# MoteinoM0_mic_v0_3.net
KiCad netlist of a schematic drawn in EAGLE
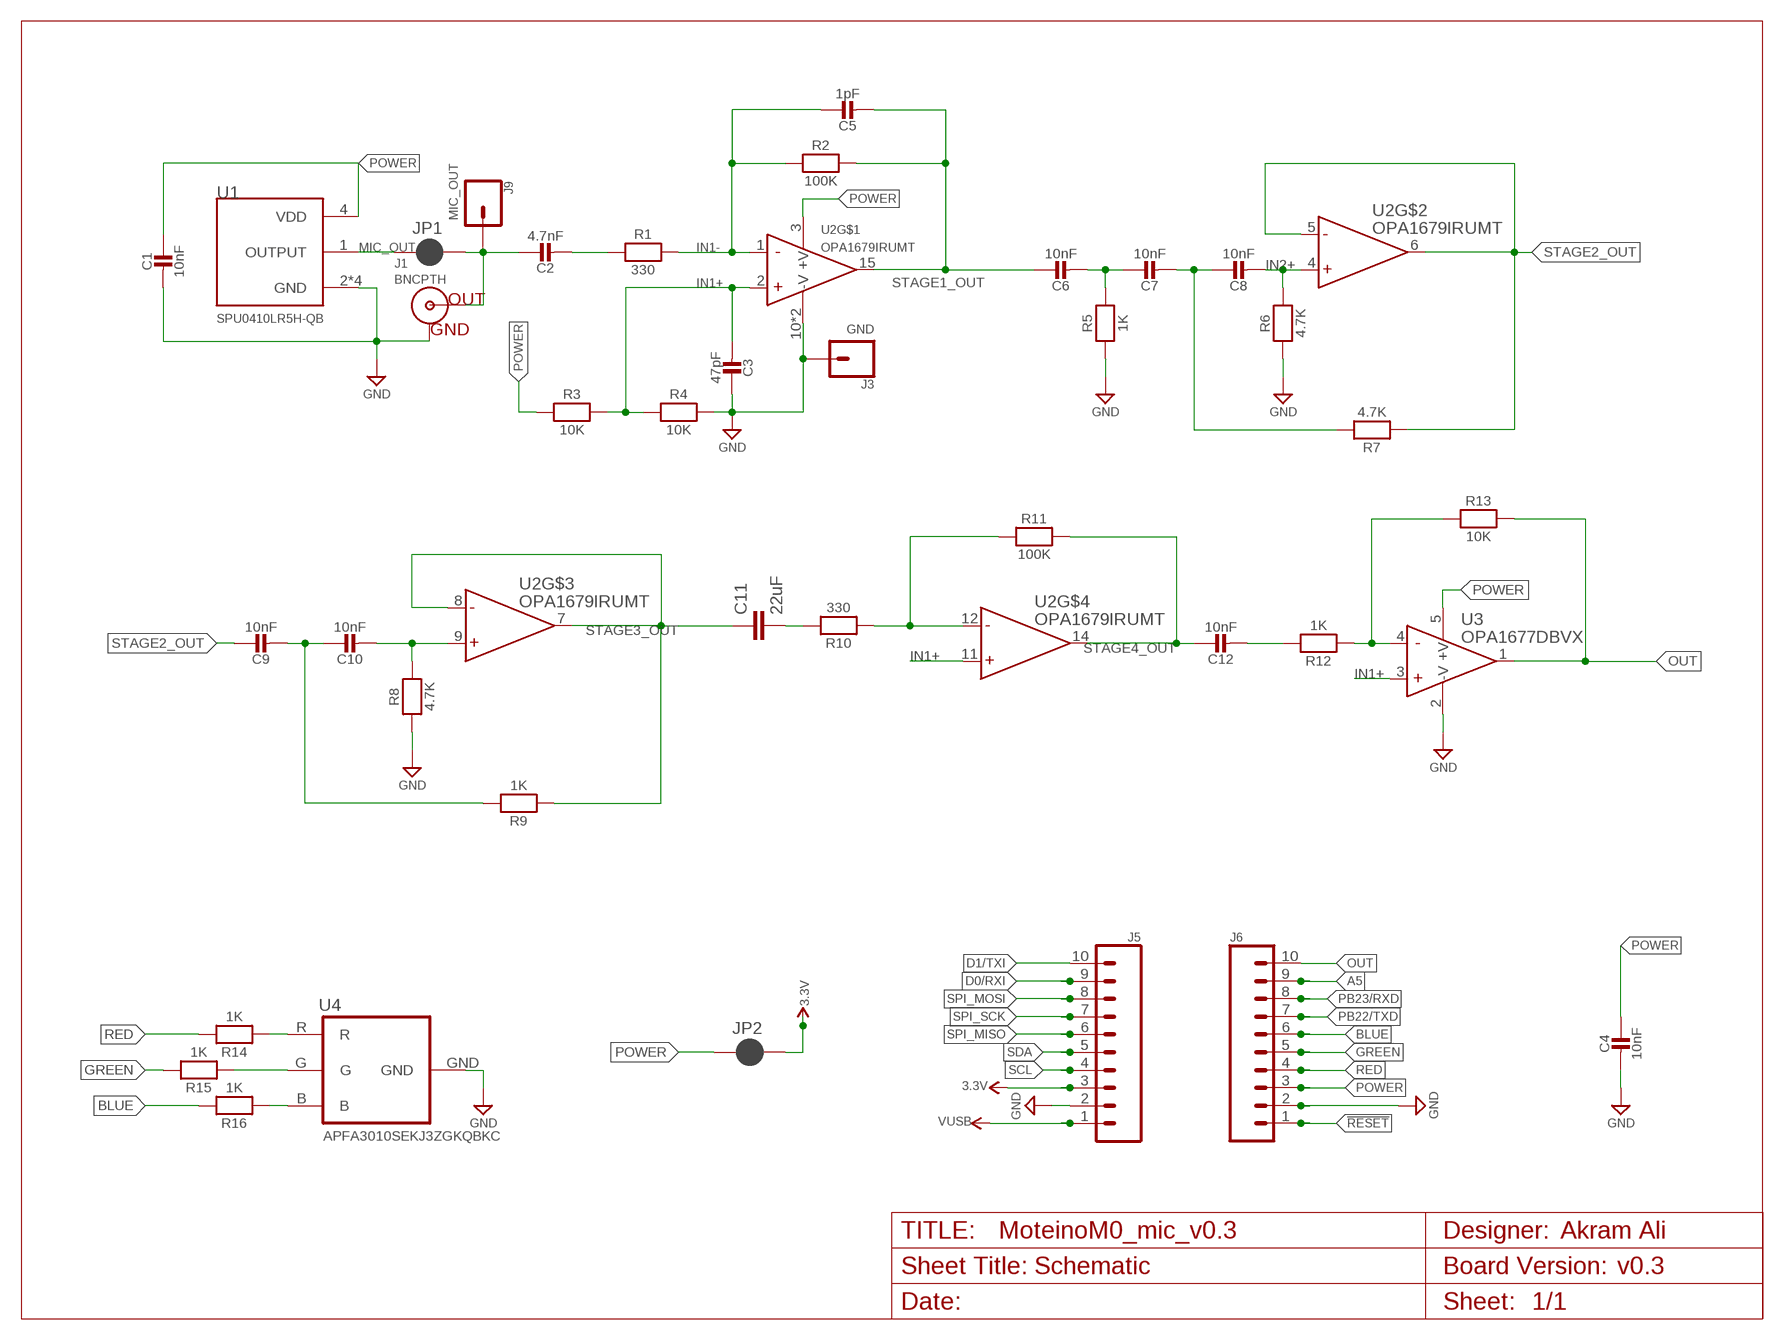
[diagram p0: schematic, sheet 1]

(export (version "E")
  (design (tool "Eeschema 10.0.6"))
  (components
    (comp (ref "C1")
      (value "10nF")
      (footprint "eagle-import:MICROBUILDER__0402MP")
      (fields (field (name "MPN") "GRM155R71H104KE14J"))
      (libsource (lib "eagle-import") (part "MICROBUILDER_CAP_CERAMIC_0402MP"))
    )
    (comp (ref "C2")
      (value "4.7nF")
      (footprint "eagle-import:MICROBUILDER__0402MP")
      (fields (field (name "MPN") "GRM155R71H104KE14J"))
      (libsource (lib "eagle-import") (part "MICROBUILDER_CAP_CERAMIC_0402MP"))
    )
    (comp (ref "C3")
      (value "47pF")
      (footprint "eagle-import:MICROBUILDER__0402MP")
      (fields (field (name "MPN") "GRM155R71H104KE14J"))
      (libsource (lib "eagle-import") (part "MICROBUILDER_CAP_CERAMIC_0402MP"))
    )
    (comp (ref "C4")
      (value "10nF")
      (footprint "eagle-import:MICROBUILDER__0402MP")
      (fields (field (name "MPN") "GRM155R71H104KE14J"))
      (libsource (lib "eagle-import") (part "MICROBUILDER_CAP_CERAMIC_0402MP"))
    )
    (comp (ref "C5")
      (value "1pF")
      (footprint "eagle-import:MICROBUILDER__0402MP")
      (fields (field (name "MPN") "GRM155R71H104KE14J"))
      (libsource (lib "eagle-import") (part "MICROBUILDER_CAP_CERAMIC_0402MP"))
    )
    (comp (ref "C6")
      (value "10nF")
      (footprint "eagle-import:MICROBUILDER__0402MP")
      (fields (field (name "MPN") "GRM155R71H104KE14J"))
      (libsource (lib "eagle-import") (part "MICROBUILDER_CAP_CERAMIC_0402MP"))
    )
    (comp (ref "C7")
      (value "10nF")
      (footprint "eagle-import:MICROBUILDER__0402MP")
      (fields (field (name "MPN") "GRM155R71H104KE14J"))
      (libsource (lib "eagle-import") (part "MICROBUILDER_CAP_CERAMIC_0402MP"))
    )
    (comp (ref "C8")
      (value "10nF")
      (footprint "eagle-import:MICROBUILDER__0402MP")
      (fields (field (name "MPN") "GRM155R71H104KE14J"))
      (libsource (lib "eagle-import") (part "MICROBUILDER_CAP_CERAMIC_0402MP"))
    )
    (comp (ref "C9")
      (value "10nF")
      (footprint "eagle-import:MICROBUILDER__0402MP")
      (fields (field (name "MPN") "GRM155R71H104KE14J"))
      (libsource (lib "eagle-import") (part "MICROBUILDER_CAP_CERAMIC_0402MP"))
    )
    (comp (ref "C10")
      (value "10nF")
      (footprint "eagle-import:MICROBUILDER__0402MP")
      (fields (field (name "MPN") "GRM155R71H104KE14J"))
      (libsource (lib "eagle-import") (part "MICROBUILDER_CAP_CERAMIC_0402MP"))
    )
    (comp (ref "C11")
      (value "22uF")
      (footprint "eagle-import:0805")
      (libsource (lib "eagle-import") (part "CAP0805"))
    )
    (comp (ref "C12")
      (value "10nF")
      (footprint "eagle-import:MICROBUILDER__0402MP")
      (fields (field (name "MPN") "GRM155R71H104KE14J"))
      (libsource (lib "eagle-import") (part "MICROBUILDER_CAP_CERAMIC_0402MP"))
    )
    (comp (ref "J1")
      (value "BNCPTH")
      (footprint "eagle-import:BNC")
      (libsource (lib "eagle-import") (part "BNCPTH"))
    )
    (comp (ref "J3")
      (value "GND")
      (footprint "eagle-import:1X01")
      (libsource (lib "eagle-import") (part "CONN_01"))
    )
    (comp (ref "J5")
      (value "CONN_10NO_SILK_PTH_FEMALE")
      (footprint "eagle-import:1X10_NO_SILK")
      (libsource (lib "eagle-import") (part "CONN_10NO_SILK_PTH_FEMALE"))
    )
    (comp (ref "J6")
      (value "CONN_10NO_SILK_PTH_FEMALE")
      (footprint "eagle-import:1X10_NO_SILK")
      (libsource (lib "eagle-import") (part "CONN_10NO_SILK_PTH_FEMALE"))
    )
    (comp (ref "J9")
      (value "MIC_OUT")
      (footprint "eagle-import:1X01")
      (libsource (lib "eagle-import") (part "CONN_01"))
    )
    (comp (ref "JP1")
      (value "JUMPER-SMT_2_NC_PASTE_SILK")
      (footprint "eagle-import:SMT-JUMPER_2_NC_PASTE_SILK")
      (libsource (lib "eagle-import") (part "JUMPER-SMT_2_NC_PASTE_SILK"))
    )
    (comp (ref "JP2")
      (value "JUMPER-SMT_2_NC_PASTE_SILK")
      (footprint "eagle-import:SMT-JUMPER_2_NC_PASTE_SILK")
      (libsource (lib "eagle-import") (part "JUMPER-SMT_2_NC_PASTE_SILK"))
    )
    (comp (ref "R1")
      (value "330")
      (footprint "eagle-import:MICROBUILDER__0402MP")
      (fields (field (name "MPN") "RC0402FR-074K7P"))
      (libsource (lib "eagle-import") (part "MICROBUILDER_RESISTOR_0402MP"))
    )
    (comp (ref "R2")
      (value "100K")
      (footprint "eagle-import:MICROBUILDER__0402MP")
      (fields (field (name "MPN") "RC0402FR-074K7P"))
      (libsource (lib "eagle-import") (part "MICROBUILDER_RESISTOR_0402MP"))
    )
    (comp (ref "R3")
      (value "10K")
      (footprint "eagle-import:MICROBUILDER__0402MP")
      (fields (field (name "MPN") "RC0402FR-074K7P"))
      (libsource (lib "eagle-import") (part "MICROBUILDER_RESISTOR_0402MP"))
    )
    (comp (ref "R4")
      (value "10K")
      (footprint "eagle-import:MICROBUILDER__0402MP")
      (fields (field (name "MPN") "RC0402FR-074K7P"))
      (libsource (lib "eagle-import") (part "MICROBUILDER_RESISTOR_0402MP"))
    )
    (comp (ref "R5")
      (value "1K")
      (footprint "eagle-import:MICROBUILDER__0402MP")
      (fields (field (name "MPN") "RC0402FR-074K7P"))
      (libsource (lib "eagle-import") (part "MICROBUILDER_RESISTOR_0402MP"))
    )
    (comp (ref "R6")
      (value "4.7K")
      (footprint "eagle-import:MICROBUILDER__0402MP")
      (fields (field (name "MPN") "RC0402FR-074K7P"))
      (libsource (lib "eagle-import") (part "MICROBUILDER_RESISTOR_0402MP"))
    )
    (comp (ref "R7")
      (value "4.7K")
      (footprint "eagle-import:MICROBUILDER__0402MP")
      (fields (field (name "MPN") "RC0402FR-074K7P"))
      (libsource (lib "eagle-import") (part "MICROBUILDER_RESISTOR_0402MP"))
    )
    (comp (ref "R8")
      (value "4.7K")
      (footprint "eagle-import:MICROBUILDER__0402MP")
      (fields (field (name "MPN") "RC0402FR-074K7P"))
      (libsource (lib "eagle-import") (part "MICROBUILDER_RESISTOR_0402MP"))
    )
    (comp (ref "R9")
      (value "1K")
      (footprint "eagle-import:MICROBUILDER__0402MP")
      (fields (field (name "MPN") "RC0402FR-074K7P"))
      (libsource (lib "eagle-import") (part "MICROBUILDER_RESISTOR_0402MP"))
    )
    (comp (ref "R10")
      (value "330")
      (footprint "eagle-import:MICROBUILDER__0402MP")
      (fields (field (name "MPN") "RC0402FR-074K7P"))
      (libsource (lib "eagle-import") (part "MICROBUILDER_RESISTOR_0402MP"))
    )
    (comp (ref "R11")
      (value "100K")
      (footprint "eagle-import:MICROBUILDER__0402MP")
      (fields (field (name "MPN") "RC0402FR-074K7P"))
      (libsource (lib "eagle-import") (part "MICROBUILDER_RESISTOR_0402MP"))
    )
    (comp (ref "R12")
      (value "1K")
      (footprint "eagle-import:MICROBUILDER__0402MP")
      (fields (field (name "MPN") "RC0402FR-074K7P"))
      (libsource (lib "eagle-import") (part "MICROBUILDER_RESISTOR_0402MP"))
    )
    (comp (ref "R13")
      (value "10K")
      (footprint "eagle-import:MICROBUILDER__0402MP")
      (fields (field (name "MPN") "RC0402FR-074K7P"))
      (libsource (lib "eagle-import") (part "MICROBUILDER_RESISTOR_0402MP"))
    )
    (comp (ref "R14")
      (value "1K")
      (footprint "eagle-import:MICROBUILDER__0402MP")
      (fields (field (name "MPN") "RC0402FR-074K7P"))
      (libsource (lib "eagle-import") (part "MICROBUILDER_RESISTOR_0402MP"))
    )
    (comp (ref "R15")
      (value "1K")
      (footprint "eagle-import:MICROBUILDER__0402MP")
      (fields (field (name "MPN") "RC0402FR-074K7P"))
      (libsource (lib "eagle-import") (part "MICROBUILDER_RESISTOR_0402MP"))
    )
    (comp (ref "R16")
      (value "1K")
      (footprint "eagle-import:MICROBUILDER__0402MP")
      (fields (field (name "MPN") "RC0402FR-074K7P"))
      (libsource (lib "eagle-import") (part "MICROBUILDER_RESISTOR_0402MP"))
    )
    (comp (ref "U1")
      (value "SPU0410LR5H-QB")
      (footprint "eagle-import:XDCR_SPU0410LR5H-QB")
      (fields (field (name "MF") "Knowles"))
      (libsource (lib "eagle-import") (part "SPU0410LR5H-QB"))
    )
    (comp (ref "U2")
      (value "OPA1679IRUMT")
      (footprint "eagle-import:QFN65P400X400X80-17N")
      (libsource (lib "eagle-import") (part "OPA1679IRUMT"))
    )
    (comp (ref "U3")
      (value "OPA1677DBVX")
      (footprint "eagle-import:SOT23-5")
      (libsource (lib "eagle-import") (part "OPA1677DBVX"))
    )
    (comp (ref "U4")
      (value "APFA3010SEKJ3ZGKQBKC")
      (footprint "eagle-import:SMD-RA-4")
      (libsource (lib "eagle-import") (part "APFA3010SEKJ3ZGKQBKC"))
    )
  )
  (nets
    (net (code "1") (name "/IN1+") (class "Default")
      (node (ref "C3") (pin "2") (pinfunction "2_2") (pintype "passive"))
      (node (ref "R3") (pin "2") (pinfunction "2_2") (pintype "passive"))
      (node (ref "R4") (pin "1") (pinfunction "1_1") (pintype "passive"))
      (node (ref "U2") (pin "11") (pinfunction "+IN_11") (pintype "input"))
      (node (ref "U2") (pin "2") (pinfunction "+IN_2") (pintype "input"))
      (node (ref "U3") (pin "3") (pinfunction "+IN_3") (pintype "input"))
    )
    (net (code "2") (name "/IN1-") (class "Default")
      (node (ref "C5") (pin "1") (pinfunction "1_1") (pintype "passive"))
      (node (ref "R1") (pin "2") (pinfunction "2_2") (pintype "passive"))
      (node (ref "R2") (pin "1") (pinfunction "1_1") (pintype "passive"))
      (node (ref "U2") (pin "1") (pinfunction "-IN_1") (pintype "input"))
    )
    (net (code "3") (name "/IN2+") (class "Default")
      (node (ref "C8") (pin "2") (pinfunction "2_2") (pintype "passive"))
      (node (ref "R6") (pin "2") (pinfunction "2_2") (pintype "passive"))
      (node (ref "U2") (pin "4") (pinfunction "+IN_4") (pintype "input"))
    )
    (net (code "4") (name "/MIC_OUT") (class "Default")
      (node (ref "C2") (pin "1") (pinfunction "1_1") (pintype "passive"))
      (node (ref "J1") (pin "S") (pinfunction "OUT_S") (pintype "bidirectional"))
      (node (ref "J9") (pin "1") (pinfunction "1_1") (pintype "passive"))
      (node (ref "JP1") (pin "2") (pinfunction "2_2") (pintype "passive"))
    )
    (net (code "5") (name "/STAGE1_OUT") (class "Default")
      (node (ref "C5") (pin "2") (pinfunction "2_2") (pintype "passive"))
      (node (ref "C6") (pin "1") (pinfunction "1_1") (pintype "passive"))
      (node (ref "R2") (pin "2") (pinfunction "2_2") (pintype "passive"))
      (node (ref "U2") (pin "15") (pinfunction "OUT_15") (pintype "output"))
    )
    (net (code "6") (name "/STAGE3_OUT") (class "Default")
      (node (ref "C11") (pin "1") (pinfunction "1_1") (pintype "passive"))
      (node (ref "R9") (pin "1") (pinfunction "1_1") (pintype "passive"))
      (node (ref "U2") (pin "7") (pinfunction "OUT_7") (pintype "output"))
      (node (ref "U2") (pin "8") (pinfunction "-IN_8") (pintype "input"))
    )
    (net (code "7") (name "/STAGE4_OUT") (class "Default")
      (node (ref "C12") (pin "1") (pinfunction "1_1") (pintype "passive"))
      (node (ref "R11") (pin "2") (pinfunction "2_2") (pintype "passive"))
      (node (ref "U2") (pin "14") (pinfunction "OUT_14") (pintype "output"))
    )
    (net (code "8") (name "/~{RESET}") (class "Default")
      (node (ref "J6") (pin "1") (pinfunction "1_1") (pintype "passive"))
    )
    (net (code "9") (name "3.3V") (class "Default")
      (node (ref "J5") (pin "3") (pinfunction "3_3") (pintype "passive"))
      (node (ref "JP2") (pin "2") (pinfunction "2_2") (pintype "passive"))
    )
    (net (code "10") (name "A5") (class "Default")
      (node (ref "J6") (pin "9") (pinfunction "9_9") (pintype "passive"))
    )
    (net (code "11") (name "BLUE") (class "Default")
      (node (ref "J6") (pin "6") (pinfunction "6_6") (pintype "passive"))
      (node (ref "R16") (pin "2") (pinfunction "2_2") (pintype "passive"))
    )
    (net (code "12") (name "D0{slash}RXI") (class "Default")
      (node (ref "J5") (pin "9") (pinfunction "9_9") (pintype "passive"))
    )
    (net (code "13") (name "D1{slash}TXI") (class "Default")
      (node (ref "J5") (pin "10") (pinfunction "10_10") (pintype "passive"))
    )
    (net (code "14") (name "GND") (class "Default")
      (node (ref "C1") (pin "2") (pinfunction "2_2") (pintype "passive"))
      (node (ref "C3") (pin "1") (pinfunction "1_1") (pintype "passive"))
      (node (ref "C4") (pin "2") (pinfunction "2_2") (pintype "passive"))
      (node (ref "J1") (pin "GND") (pinfunction "GND_GND") (pintype "bidirectional"))
      (node (ref "J3") (pin "1") (pinfunction "1_1") (pintype "passive"))
      (node (ref "J5") (pin "2") (pinfunction "2_2") (pintype "passive"))
      (node (ref "J6") (pin "2") (pinfunction "2_2") (pintype "passive"))
      (node (ref "R4") (pin "2") (pinfunction "2_2") (pintype "passive"))
      (node (ref "R5") (pin "1") (pinfunction "1_1") (pintype "passive"))
      (node (ref "R6") (pin "1") (pinfunction "1_1") (pintype "passive"))
      (node (ref "R8") (pin "1") (pinfunction "1_1") (pintype "passive"))
      (node (ref "U1") (pin "2") (pinfunction "GND_2") (pintype "power_in"))
      (node (ref "U1") (pin "3") (pinfunction "GND_3") (pintype "power_in"))
      (node (ref "U1") (pin "5") (pinfunction "GND_5") (pintype "power_in"))
      (node (ref "U1") (pin "6") (pinfunction "GND_6") (pintype "power_in"))
      (node (ref "U2") (pin "10") (pinfunction "-V_10") (pintype "power_in"))
      (node (ref "U2") (pin "17") (pinfunction "-V_17") (pintype "power_in"))
      (node (ref "U3") (pin "2") (pinfunction "-V_2") (pintype "power_in"))
      (node (ref "U4") (pin "GND") (pinfunction "GND_GND") (pintype "bidirectional"))
    )
    (net (code "15") (name "GREEN") (class "Default")
      (node (ref "J6") (pin "5") (pinfunction "5_5") (pintype "passive"))
      (node (ref "R15") (pin "2") (pinfunction "2_2") (pintype "passive"))
    )
    (net (code "16") (name "Net-(C2-Pad2)") (class "Default")
      (node (ref "C2") (pin "2") (pinfunction "2_2") (pintype "passive"))
      (node (ref "R1") (pin "1") (pinfunction "1_1") (pintype "passive"))
    )
    (net (code "17") (name "Net-(C6-Pad2)") (class "Default")
      (node (ref "C6") (pin "2") (pinfunction "2_2") (pintype "passive"))
      (node (ref "C7") (pin "1") (pinfunction "1_1") (pintype "passive"))
      (node (ref "R5") (pin "2") (pinfunction "2_2") (pintype "passive"))
    )
    (net (code "18") (name "Net-(C7-Pad2)") (class "Default")
      (node (ref "C7") (pin "2") (pinfunction "2_2") (pintype "passive"))
      (node (ref "C8") (pin "1") (pinfunction "1_1") (pintype "passive"))
      (node (ref "R7") (pin "2") (pinfunction "2_2") (pintype "passive"))
    )
    (net (code "19") (name "Net-(C10-Pad1)") (class "Default")
      (node (ref "C10") (pin "1") (pinfunction "1_1") (pintype "passive"))
      (node (ref "C9") (pin "2") (pinfunction "2_2") (pintype "passive"))
      (node (ref "R9") (pin "2") (pinfunction "2_2") (pintype "passive"))
    )
    (net (code "20") (name "Net-(C11-Pad2)") (class "Default")
      (node (ref "C11") (pin "2") (pinfunction "2_2") (pintype "passive"))
      (node (ref "R10") (pin "2") (pinfunction "2_2") (pintype "passive"))
    )
    (net (code "21") (name "Net-(C12-Pad2)") (class "Default")
      (node (ref "C12") (pin "2") (pinfunction "2_2") (pintype "passive"))
      (node (ref "R12") (pin "2") (pinfunction "2_2") (pintype "passive"))
    )
    (net (code "22") (name "Net-(R14-Pad1)") (class "Default")
      (node (ref "R14") (pin "1") (pinfunction "1_1") (pintype "passive"))
      (node (ref "U4") (pin "R") (pinfunction "R_R") (pintype "bidirectional"))
    )
    (net (code "23") (name "Net-(R15-Pad1)") (class "Default")
      (node (ref "R15") (pin "1") (pinfunction "1_1") (pintype "passive"))
      (node (ref "U4") (pin "G") (pinfunction "G_G") (pintype "bidirectional"))
    )
    (net (code "24") (name "Net-(R16-Pad1)") (class "Default")
      (node (ref "R16") (pin "1") (pinfunction "1_1") (pintype "passive"))
      (node (ref "U4") (pin "B") (pinfunction "B_B") (pintype "bidirectional"))
    )
    (net (code "25") (name "Net-(U1-OUTPUT)") (class "Default")
      (node (ref "JP1") (pin "1") (pinfunction "1_1") (pintype "passive"))
      (node (ref "U1") (pin "1") (pinfunction "OUTPUT_1") (pintype "output"))
    )
    (net (code "26") (name "Net-(U2C-+IN)") (class "Default")
      (node (ref "C10") (pin "2") (pinfunction "2_2") (pintype "passive"))
      (node (ref "R8") (pin "2") (pinfunction "2_2") (pintype "passive"))
      (node (ref "U2") (pin "9") (pinfunction "+IN_9") (pintype "input"))
    )
    (net (code "27") (name "Net-(U2D--IN)") (class "Default")
      (node (ref "R10") (pin "1") (pinfunction "1_1") (pintype "passive"))
      (node (ref "R11") (pin "1") (pinfunction "1_1") (pintype "passive"))
      (node (ref "U2") (pin "12") (pinfunction "-IN_12") (pintype "input"))
    )
    (net (code "28") (name "Net-(U3--IN)") (class "Default")
      (node (ref "R12") (pin "1") (pinfunction "1_1") (pintype "passive"))
      (node (ref "R13") (pin "1") (pinfunction "1_1") (pintype "passive"))
      (node (ref "U3") (pin "4") (pinfunction "-IN_4") (pintype "input"))
    )
    (net (code "29") (name "OUT") (class "Default")
      (node (ref "J6") (pin "10") (pinfunction "10_10") (pintype "passive"))
      (node (ref "R13") (pin "2") (pinfunction "2_2") (pintype "passive"))
      (node (ref "U3") (pin "1") (pinfunction "OUT_1") (pintype "output"))
    )
    (net (code "30") (name "PB22{slash}TXD") (class "Default")
      (node (ref "J6") (pin "7") (pinfunction "7_7") (pintype "passive"))
    )
    (net (code "31") (name "PB23{slash}RXD") (class "Default")
      (node (ref "J6") (pin "8") (pinfunction "8_8") (pintype "passive"))
    )
    (net (code "32") (name "POWER") (class "Default")
      (node (ref "C1") (pin "1") (pinfunction "1_1") (pintype "passive"))
      (node (ref "C4") (pin "1") (pinfunction "1_1") (pintype "passive"))
      (node (ref "J6") (pin "3") (pinfunction "3_3") (pintype "passive"))
      (node (ref "JP2") (pin "1") (pinfunction "1_1") (pintype "passive"))
      (node (ref "R3") (pin "1") (pinfunction "1_1") (pintype "passive"))
      (node (ref "U1") (pin "4") (pinfunction "VDD_4") (pintype "power_in"))
      (node (ref "U2") (pin "3") (pinfunction "+V_3") (pintype "power_in"))
      (node (ref "U3") (pin "5") (pinfunction "+V_5") (pintype "power_in"))
    )
    (net (code "33") (name "RED") (class "Default")
      (node (ref "J6") (pin "4") (pinfunction "4_4") (pintype "passive"))
      (node (ref "R14") (pin "2") (pinfunction "2_2") (pintype "passive"))
    )
    (net (code "34") (name "SCL") (class "Default")
      (node (ref "J5") (pin "4") (pinfunction "4_4") (pintype "passive"))
    )
    (net (code "35") (name "SDA") (class "Default")
      (node (ref "J5") (pin "5") (pinfunction "5_5") (pintype "passive"))
    )
    (net (code "36") (name "SPI_MISO") (class "Default")
      (node (ref "J5") (pin "6") (pinfunction "6_6") (pintype "passive"))
    )
    (net (code "37") (name "SPI_MOSI") (class "Default")
      (node (ref "J5") (pin "8") (pinfunction "8_8") (pintype "passive"))
    )
    (net (code "38") (name "SPI_SCK") (class "Default")
      (node (ref "J5") (pin "7") (pinfunction "7_7") (pintype "passive"))
    )
    (net (code "39") (name "STAGE2_OUT") (class "Default")
      (node (ref "C9") (pin "1") (pinfunction "1_1") (pintype "passive"))
      (node (ref "R7") (pin "1") (pinfunction "1_1") (pintype "passive"))
      (node (ref "U2") (pin "5") (pinfunction "-IN_5") (pintype "input"))
      (node (ref "U2") (pin "6") (pinfunction "OUT_6") (pintype "output"))
    )
    (net (code "40") (name "VUSB") (class "Default")
      (node (ref "J5") (pin "1") (pinfunction "1_1") (pintype "passive"))
    )
  )
)
